# DISCRETE_IF.net
KiCad netlist of a schematic drawn in Altium Designer
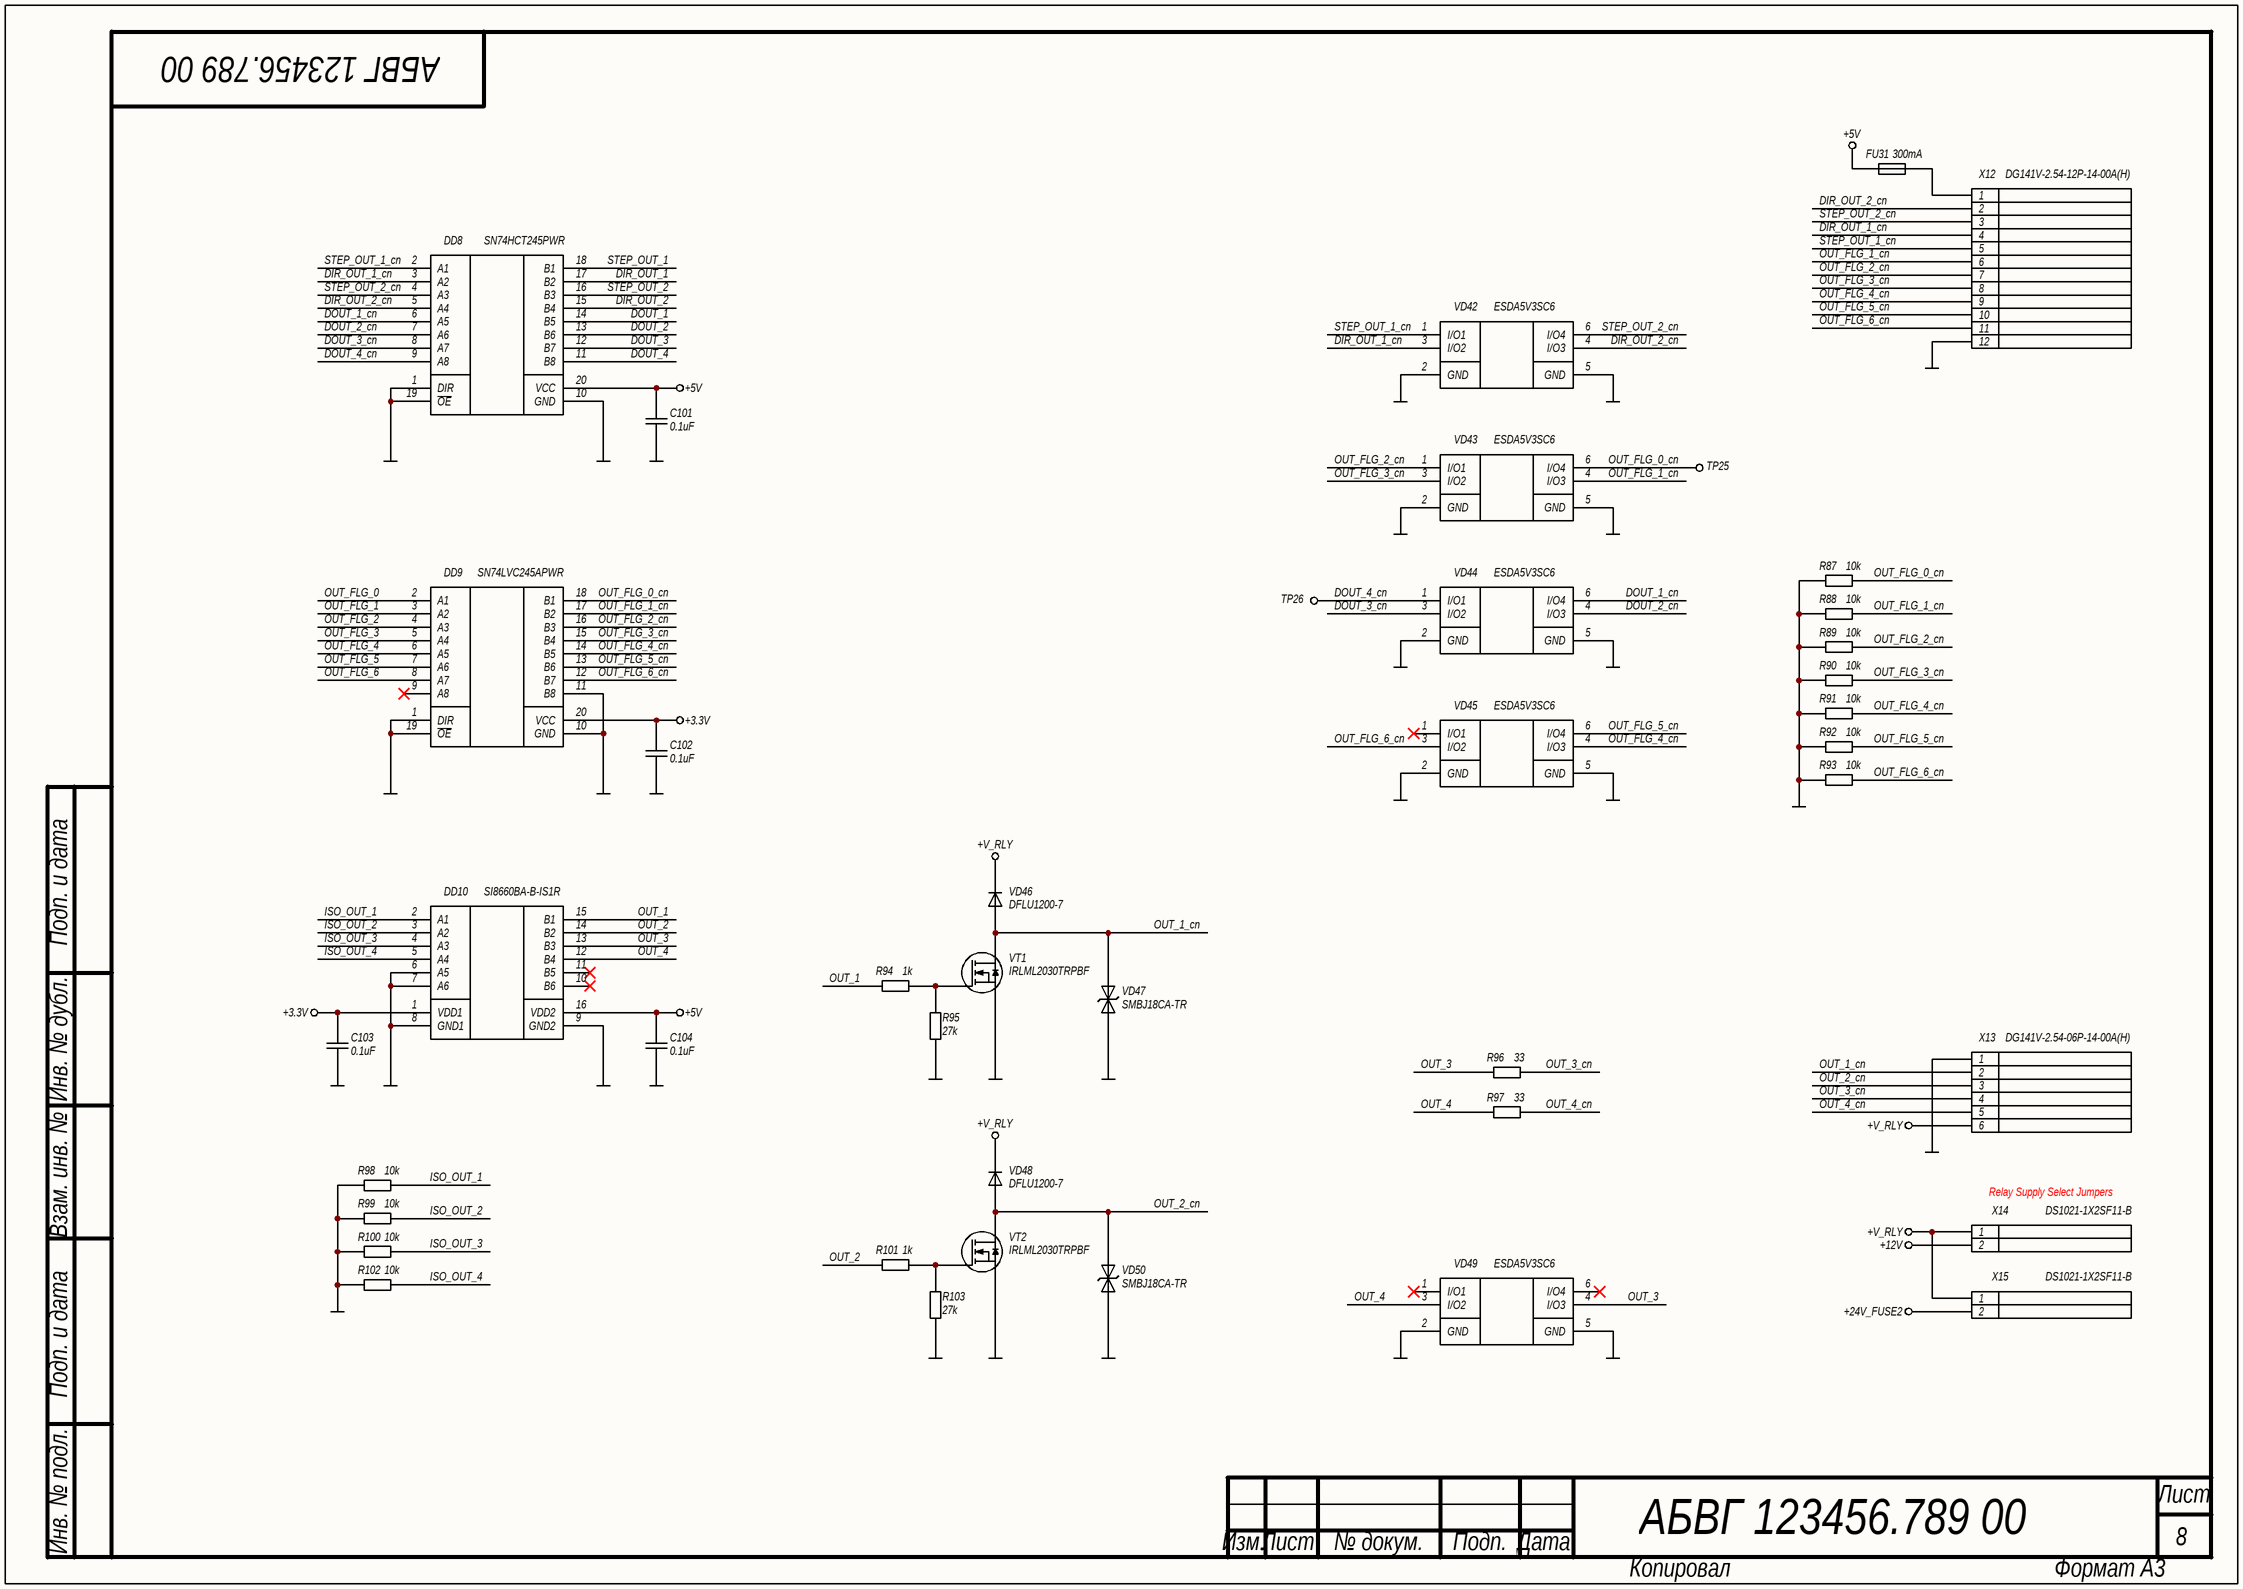
[diagram p0: DISCRETE_IF.SchDoc]

(export (version "E")
  (design (tool "Eeschema 10.0.6"))
  (components
    (comp (ref "C101")
      (value "0.1uF")
      (footprint "C0603N")
      (description "Конденсатор")
      (libsource (lib "Components Library") (part "CAP_FIXED"))
    )
    (comp (ref "C102")
      (value "0.1uF")
      (footprint "C0603N")
      (description "Конденсатор")
      (libsource (lib "Components Library") (part "CAP_FIXED"))
    )
    (comp (ref "C103")
      (value "0.1uF")
      (footprint "C0603N")
      (description "Конденсатор")
      (libsource (lib "Components Library") (part "CAP_FIXED"))
    )
    (comp (ref "C104")
      (value "0.1uF")
      (footprint "C0603N")
      (description "Конденсатор")
      (libsource (lib "Components Library") (part "CAP_FIXED"))
    )
    (comp (ref "DD8")
      (value "SN74HCT245PWR")
      (footprint "TSSOP20")
      (description "Микросхема шинный формирователь")
      (libsource (lib "Components Library") (part "SN74HCT245"))
    )
    (comp (ref "DD9")
      (value "SN74LVC245APWR")
      (footprint "TSSOP20")
      (description "Микросхема шинный формирователь")
      (libsource (lib "Components Library") (part "SN74LVC245"))
    )
    (comp (ref "DD10")
      (value "SI8660BA-B-IS1R")
      (footprint "SOIC16")
      (description "Микросхема цифровой изолятор")
      (libsource (lib "Components Library") (part "SI8660"))
    )
    (comp (ref "FU31")
      (value "300mA")
      (footprint "MF-MSMF")
      (description "Плавкий предохранитель")
      (libsource (lib "Components Library") (part "FUSE"))
    )
    (comp (ref "R87")
      (value "10k")
      (footprint "R0603N")
      (description "Резистор")
      (libsource (lib "Components Library") (part "RES_FIXED"))
    )
    (comp (ref "R88")
      (value "10k")
      (footprint "R0603N")
      (description "Резистор")
      (libsource (lib "Components Library") (part "RES_FIXED"))
    )
    (comp (ref "R89")
      (value "10k")
      (footprint "R0603N")
      (description "Резистор")
      (libsource (lib "Components Library") (part "RES_FIXED"))
    )
    (comp (ref "R90")
      (value "10k")
      (footprint "R0603N")
      (description "Резистор")
      (libsource (lib "Components Library") (part "RES_FIXED"))
    )
    (comp (ref "R91")
      (value "10k")
      (footprint "R0603N")
      (description "Резистор")
      (libsource (lib "Components Library") (part "RES_FIXED"))
    )
    (comp (ref "R92")
      (value "10k")
      (footprint "R0603N")
      (description "Резистор")
      (libsource (lib "Components Library") (part "RES_FIXED"))
    )
    (comp (ref "R93")
      (value "10k")
      (footprint "R0603N")
      (description "Резистор")
      (libsource (lib "Components Library") (part "RES_FIXED"))
    )
    (comp (ref "R94")
      (value "1k")
      (footprint "R0603N")
      (description "Резистор")
      (libsource (lib "Components Library") (part "RES_FIXED"))
    )
    (comp (ref "R95")
      (value "27k")
      (footprint "R0603N")
      (description "Резистор")
      (libsource (lib "") (part "RES_FIXED_1"))
    )
    (comp (ref "R96")
      (value "33")
      (footprint "R0603N")
      (description "Резистор")
      (libsource (lib "Components Library") (part "RES_FIXED"))
    )
    (comp (ref "R97")
      (value "33")
      (footprint "R0603N")
      (description "Резистор")
      (libsource (lib "Components Library") (part "RES_FIXED"))
    )
    (comp (ref "R98")
      (value "10k")
      (footprint "R0603N")
      (description "Резистор")
      (libsource (lib "Components Library") (part "RES_FIXED"))
    )
    (comp (ref "R99")
      (value "10k")
      (footprint "R0603N")
      (description "Резистор")
      (libsource (lib "Components Library") (part "RES_FIXED"))
    )
    (comp (ref "R100")
      (value "10k")
      (footprint "R0603N")
      (description "Резистор")
      (libsource (lib "Components Library") (part "RES_FIXED"))
    )
    (comp (ref "R101")
      (value "1k")
      (footprint "R0603N")
      (description "Резистор")
      (libsource (lib "Components Library") (part "RES_FIXED"))
    )
    (comp (ref "R102")
      (value "10k")
      (footprint "R0603N")
      (description "Резистор")
      (libsource (lib "Components Library") (part "RES_FIXED"))
    )
    (comp (ref "R103")
      (value "27k")
      (footprint "R0603N")
      (description "Резистор")
      (libsource (lib "") (part "RES_FIXED_1"))
    )
    (comp (ref "TP25")
      (value "TEST_POINT")
      (footprint "TP_HOLE_1MM_1.5MM")
      (description "Контрольная точка")
      (libsource (lib "Components Library") (part "TEST_POINT"))
    )
    (comp (ref "TP26")
      (value "TEST_POINT")
      (footprint "TP_HOLE_1MM_1.5MM")
      (description "Контрольная точка")
      (libsource (lib "Components Library") (part "TEST_POINT"))
    )
    (comp (ref "VD42")
      (value "ESDA5V3SC6")
      (footprint "SOT23-6")
      (description "Сборка TVS диодов, 4-канальная")
      (libsource (lib "Components Library") (part "ESDAxxSC6"))
    )
    (comp (ref "VD43")
      (value "ESDA5V3SC6")
      (footprint "SOT23-6")
      (description "Сборка TVS диодов, 4-канальная")
      (libsource (lib "Components Library") (part "ESDAxxSC6"))
    )
    (comp (ref "VD44")
      (value "ESDA5V3SC6")
      (footprint "SOT23-6")
      (description "Сборка TVS диодов, 4-канальная")
      (libsource (lib "Components Library") (part "ESDAxxSC6"))
    )
    (comp (ref "VD45")
      (value "ESDA5V3SC6")
      (footprint "SOT23-6")
      (description "Сборка TVS диодов, 4-канальная")
      (libsource (lib "Components Library") (part "ESDAxxSC6"))
    )
    (comp (ref "VD46")
      (value "DFLU1200-7")
      (footprint "PowerDI123")
      (description "Диод")
      (libsource (lib "Components Library") (part "DIODE"))
    )
    (comp (ref "VD47")
      (value "SMBJ18CA-TR")
      (footprint "SMB")
      (description "TVS диод двунаправленный")
      (libsource (lib "Components Library") (part "TVS_BIDIR"))
    )
    (comp (ref "VD48")
      (value "DFLU1200-7")
      (footprint "PowerDI123")
      (description "Диод")
      (libsource (lib "Components Library") (part "DIODE"))
    )
    (comp (ref "VD49")
      (value "ESDA5V3SC6")
      (footprint "SOT23-6")
      (description "Сборка TVS диодов, 4-канальная")
      (libsource (lib "Components Library") (part "ESDAxxSC6"))
    )
    (comp (ref "VD50")
      (value "SMBJ18CA-TR")
      (footprint "SMB")
      (description "TVS диод двунаправленный")
      (libsource (lib "Components Library") (part "TVS_BIDIR"))
    )
    (comp (ref "VT1")
      (value "IRLML2030TRPBF")
      (footprint "SOT23")
      (description "МОП транзистор, N-канальный")
      (libsource (lib "Components Library") (part "N-MOS 3 LEADS_G1"))
    )
    (comp (ref "VT2")
      (value "IRLML2030TRPBF")
      (footprint "SOT23")
      (description "МОП транзистор, N-канальный")
      (libsource (lib "Components Library") (part "N-MOS 3 LEADS_G1"))
    )
    (comp (ref "X12")
      (value "DG141V-2.54-12P-14-00A(H)")
      (footprint "DG141V-2.54-12P-14-00A(H)")
      (description "Разъем, 12 контактов")
      (libsource (lib "Components Library") (part "Connector 12"))
    )
    (comp (ref "X13")
      (value "DG141V-2.54-06P-14-00A(H)")
      (footprint "DG141V-2.54-06P-14-00A(H)")
      (description "Разъем, 6 контактов")
      (libsource (lib "Components Library") (part "Connector 6"))
    )
    (comp (ref "X14")
      (value "DS1021-1X2SF11-B")
      (footprint "2.54_2X1_HEADER")
      (description "Разъем, 2 контакта")
      (libsource (lib "Components Library") (part "Connector 2"))
    )
    (comp (ref "X15")
      (value "DS1021-1X2SF11-B")
      (footprint "2.54_2X1_HEADER")
      (description "Разъем, 2 контакта")
      (libsource (lib "Components Library") (part "Connector 2"))
    )
  )
  (nets
    (net (code "1") (name "+3.3V") (class "Default")
      (node (ref "C102") (pin "2") (pinfunction "2_2") (pintype "passive"))
      (node (ref "C103") (pin "2") (pinfunction "2_2") (pintype "passive"))
      (node (ref "DD10") (pin "1") (pinfunction "VDD1_1") (pintype "power_in"))
      (node (ref "DD9") (pin "20") (pinfunction "VCC_20") (pintype "power_in"))
    )
    (net (code "2") (name "+5V") (class "Default")
      (node (ref "C101") (pin "2") (pinfunction "2_2") (pintype "passive"))
      (node (ref "C104") (pin "2") (pinfunction "2_2") (pintype "passive"))
      (node (ref "DD10") (pin "16") (pinfunction "VDD2_16") (pintype "power_in"))
      (node (ref "DD8") (pin "20") (pinfunction "VCC_20") (pintype "power_in"))
      (node (ref "FU31") (pin "1") (pinfunction "1_1") (pintype "passive"))
    )
    (net (code "3") (name "+12V") (class "Default")
      (node (ref "X14") (pin "2") (pinfunction "2_2") (pintype "power_in"))
    )
    (net (code "4") (name "+24V_FUSE2") (class "Default")
      (node (ref "X15") (pin "2") (pinfunction "2_2") (pintype "power_in"))
    )
    (net (code "5") (name "+V_RLY") (class "Default")
      (node (ref "VD46") (pin "1") (pinfunction "K_1") (pintype "passive"))
      (node (ref "VD48") (pin "1") (pinfunction "K_1") (pintype "passive"))
      (node (ref "X13") (pin "6") (pinfunction "6_6") (pintype "power_in"))
      (node (ref "X14") (pin "1") (pinfunction "1_1") (pintype "power_in"))
      (node (ref "X15") (pin "1") (pinfunction "1_1") (pintype "power_in"))
    )
    (net (code "6") (name "/DIR_OUT_1") (class "Default")
      (node (ref "DD8") (pin "17") (pinfunction "B2_17") (pintype "power_in"))
    )
    (net (code "7") (name "/DIR_OUT_1_cn") (class "Default")
      (node (ref "DD8") (pin "3") (pinfunction "A2_3") (pintype "power_in"))
      (node (ref "VD42") (pin "3") (pinfunction "I/O2_3") (pintype "power_in"))
      (node (ref "X12") (pin "4") (pinfunction "4_4") (pintype "power_in"))
    )
    (net (code "8") (name "/DIR_OUT_2") (class "Default")
      (node (ref "DD8") (pin "15") (pinfunction "B4_15") (pintype "power_in"))
    )
    (net (code "9") (name "/DIR_OUT_2_cn") (class "Default")
      (node (ref "DD8") (pin "5") (pinfunction "A4_5") (pintype "power_in"))
      (node (ref "VD42") (pin "4") (pinfunction "I/O3_4") (pintype "power_in"))
      (node (ref "X12") (pin "2") (pinfunction "2_2") (pintype "power_in"))
    )
    (net (code "10") (name "/DOUT_1") (class "Default")
      (node (ref "DD8") (pin "14") (pinfunction "B5_14") (pintype "power_in"))
    )
    (net (code "11") (name "/DOUT_1_cn") (class "Default")
      (node (ref "DD8") (pin "6") (pinfunction "A5_6") (pintype "power_in"))
      (node (ref "VD44") (pin "6") (pinfunction "I/O4_6") (pintype "power_in"))
    )
    (net (code "12") (name "/DOUT_2") (class "Default")
      (node (ref "DD8") (pin "13") (pinfunction "B6_13") (pintype "power_in"))
    )
    (net (code "13") (name "/DOUT_2_cn") (class "Default")
      (node (ref "DD8") (pin "7") (pinfunction "A6_7") (pintype "power_in"))
      (node (ref "VD44") (pin "4") (pinfunction "I/O3_4") (pintype "power_in"))
    )
    (net (code "14") (name "/DOUT_3") (class "Default")
      (node (ref "DD8") (pin "12") (pinfunction "B7_12") (pintype "power_in"))
    )
    (net (code "15") (name "/DOUT_3_cn") (class "Default")
      (node (ref "DD8") (pin "8") (pinfunction "A7_8") (pintype "power_in"))
      (node (ref "VD44") (pin "3") (pinfunction "I/O2_3") (pintype "power_in"))
    )
    (net (code "16") (name "/DOUT_4") (class "Default")
      (node (ref "DD8") (pin "11") (pinfunction "B8_11") (pintype "power_in"))
    )
    (net (code "17") (name "/DOUT_4_cn") (class "Default")
      (node (ref "DD8") (pin "9") (pinfunction "A8_9") (pintype "power_in"))
      (node (ref "TP26") (pin "1") (pinfunction "1_1") (pintype "passive"))
      (node (ref "VD44") (pin "1") (pinfunction "I/O1_1") (pintype "power_in"))
    )
    (net (code "18") (name "/ISO_OUT_1") (class "Default")
      (node (ref "DD10") (pin "2") (pinfunction "A1_2") (pintype "power_in"))
      (node (ref "R98") (pin "1") (pinfunction "1_1") (pintype "passive"))
    )
    (net (code "19") (name "/ISO_OUT_2") (class "Default")
      (node (ref "DD10") (pin "3") (pinfunction "A2_3") (pintype "power_in"))
      (node (ref "R99") (pin "1") (pinfunction "1_1") (pintype "passive"))
    )
    (net (code "20") (name "/ISO_OUT_3") (class "Default")
      (node (ref "DD10") (pin "4") (pinfunction "A3_4") (pintype "power_in"))
      (node (ref "R100") (pin "1") (pinfunction "1_1") (pintype "passive"))
    )
    (net (code "21") (name "/ISO_OUT_4") (class "Default")
      (node (ref "DD10") (pin "5") (pinfunction "A4_5") (pintype "power_in"))
      (node (ref "R102") (pin "1") (pinfunction "1_1") (pintype "passive"))
    )
    (net (code "22") (name "/OUT_1") (class "Default")
      (node (ref "DD10") (pin "15") (pinfunction "B1_15") (pintype "power_in"))
      (node (ref "R94") (pin "2") (pinfunction "2_2") (pintype "passive"))
    )
    (net (code "23") (name "/OUT_1_cn") (class "Default")
      (node (ref "VD46") (pin "2") (pinfunction "A_2") (pintype "passive"))
      (node (ref "VD47") (pin "1") (pinfunction "A1_1") (pintype "passive"))
      (node (ref "VT1") (pin "3") (pinfunction "D_3") (pintype "passive"))
      (node (ref "X13") (pin "2") (pinfunction "2_2") (pintype "power_in"))
    )
    (net (code "24") (name "/OUT_2") (class "Default")
      (node (ref "DD10") (pin "14") (pinfunction "B2_14") (pintype "power_in"))
      (node (ref "R101") (pin "2") (pinfunction "2_2") (pintype "passive"))
    )
    (net (code "25") (name "/OUT_2_cn") (class "Default")
      (node (ref "VD48") (pin "2") (pinfunction "A_2") (pintype "passive"))
      (node (ref "VD50") (pin "1") (pinfunction "A1_1") (pintype "passive"))
      (node (ref "VT2") (pin "3") (pinfunction "D_3") (pintype "passive"))
      (node (ref "X13") (pin "3") (pinfunction "3_3") (pintype "power_in"))
    )
    (net (code "26") (name "/OUT_3") (class "Default")
      (node (ref "DD10") (pin "13") (pinfunction "B3_13") (pintype "power_in"))
      (node (ref "R96") (pin "2") (pinfunction "2_2") (pintype "passive"))
      (node (ref "VD49") (pin "4") (pinfunction "I/O3_4") (pintype "power_in"))
    )
    (net (code "27") (name "/OUT_3_cn") (class "Default")
      (node (ref "R96") (pin "1") (pinfunction "1_1") (pintype "passive"))
      (node (ref "X13") (pin "4") (pinfunction "4_4") (pintype "power_in"))
    )
    (net (code "28") (name "/OUT_4") (class "Default")
      (node (ref "DD10") (pin "12") (pinfunction "B4_12") (pintype "power_in"))
      (node (ref "R97") (pin "2") (pinfunction "2_2") (pintype "passive"))
      (node (ref "VD49") (pin "3") (pinfunction "I/O2_3") (pintype "power_in"))
    )
    (net (code "29") (name "/OUT_4_cn") (class "Default")
      (node (ref "R97") (pin "1") (pinfunction "1_1") (pintype "passive"))
      (node (ref "X13") (pin "5") (pinfunction "5_5") (pintype "power_in"))
    )
    (net (code "30") (name "/OUT_FLG_0") (class "Default")
      (node (ref "DD9") (pin "2") (pinfunction "A1_2") (pintype "power_in"))
    )
    (net (code "31") (name "/OUT_FLG_0_cn") (class "Default")
      (node (ref "DD9") (pin "18") (pinfunction "B1_18") (pintype "power_in"))
      (node (ref "R87") (pin "1") (pinfunction "1_1") (pintype "passive"))
      (node (ref "TP25") (pin "1") (pinfunction "1_1") (pintype "passive"))
      (node (ref "VD43") (pin "6") (pinfunction "I/O4_6") (pintype "power_in"))
    )
    (net (code "32") (name "/OUT_FLG_1") (class "Default")
      (node (ref "DD9") (pin "3") (pinfunction "A2_3") (pintype "power_in"))
    )
    (net (code "33") (name "/OUT_FLG_1_cn") (class "Default")
      (node (ref "DD9") (pin "17") (pinfunction "B2_17") (pintype "power_in"))
      (node (ref "R88") (pin "1") (pinfunction "1_1") (pintype "passive"))
      (node (ref "VD43") (pin "4") (pinfunction "I/O3_4") (pintype "power_in"))
      (node (ref "X12") (pin "6") (pinfunction "6_6") (pintype "power_in"))
    )
    (net (code "34") (name "/OUT_FLG_2") (class "Default")
      (node (ref "DD9") (pin "4") (pinfunction "A3_4") (pintype "power_in"))
    )
    (net (code "35") (name "/OUT_FLG_2_cn") (class "Default")
      (node (ref "DD9") (pin "16") (pinfunction "B3_16") (pintype "power_in"))
      (node (ref "R89") (pin "1") (pinfunction "1_1") (pintype "passive"))
      (node (ref "VD43") (pin "1") (pinfunction "I/O1_1") (pintype "power_in"))
      (node (ref "X12") (pin "7") (pinfunction "7_7") (pintype "power_in"))
    )
    (net (code "36") (name "/OUT_FLG_3") (class "Default")
      (node (ref "DD9") (pin "5") (pinfunction "A4_5") (pintype "power_in"))
    )
    (net (code "37") (name "/OUT_FLG_3_cn") (class "Default")
      (node (ref "DD9") (pin "15") (pinfunction "B4_15") (pintype "power_in"))
      (node (ref "R90") (pin "1") (pinfunction "1_1") (pintype "passive"))
      (node (ref "VD43") (pin "3") (pinfunction "I/O2_3") (pintype "power_in"))
      (node (ref "X12") (pin "8") (pinfunction "8_8") (pintype "power_in"))
    )
    (net (code "38") (name "/OUT_FLG_4") (class "Default")
      (node (ref "DD9") (pin "6") (pinfunction "A5_6") (pintype "power_in"))
    )
    (net (code "39") (name "/OUT_FLG_4_cn") (class "Default")
      (node (ref "DD9") (pin "14") (pinfunction "B5_14") (pintype "power_in"))
      (node (ref "R91") (pin "1") (pinfunction "1_1") (pintype "passive"))
      (node (ref "VD45") (pin "4") (pinfunction "I/O3_4") (pintype "power_in"))
      (node (ref "X12") (pin "9") (pinfunction "9_9") (pintype "power_in"))
    )
    (net (code "40") (name "/OUT_FLG_5") (class "Default")
      (node (ref "DD9") (pin "7") (pinfunction "A6_7") (pintype "power_in"))
    )
    (net (code "41") (name "/OUT_FLG_5_cn") (class "Default")
      (node (ref "DD9") (pin "13") (pinfunction "B6_13") (pintype "power_in"))
      (node (ref "R92") (pin "1") (pinfunction "1_1") (pintype "passive"))
      (node (ref "VD45") (pin "6") (pinfunction "I/O4_6") (pintype "power_in"))
      (node (ref "X12") (pin "10") (pinfunction "10_10") (pintype "power_in"))
    )
    (net (code "42") (name "/OUT_FLG_6") (class "Default")
      (node (ref "DD9") (pin "8") (pinfunction "A7_8") (pintype "power_in"))
    )
    (net (code "43") (name "/OUT_FLG_6_cn") (class "Default")
      (node (ref "DD9") (pin "12") (pinfunction "B7_12") (pintype "power_in"))
      (node (ref "R93") (pin "1") (pinfunction "1_1") (pintype "passive"))
      (node (ref "VD45") (pin "3") (pinfunction "I/O2_3") (pintype "power_in"))
      (node (ref "X12") (pin "11") (pinfunction "11_11") (pintype "power_in"))
    )
    (net (code "44") (name "/STEP_OUT_1") (class "Default")
      (node (ref "DD8") (pin "18") (pinfunction "B1_18") (pintype "power_in"))
    )
    (net (code "45") (name "/STEP_OUT_1_cn") (class "Default")
      (node (ref "DD8") (pin "2") (pinfunction "A1_2") (pintype "power_in"))
      (node (ref "VD42") (pin "1") (pinfunction "I/O1_1") (pintype "power_in"))
      (node (ref "X12") (pin "5") (pinfunction "5_5") (pintype "power_in"))
    )
    (net (code "46") (name "/STEP_OUT_2") (class "Default")
      (node (ref "DD8") (pin "16") (pinfunction "B3_16") (pintype "power_in"))
    )
    (net (code "47") (name "/STEP_OUT_2_cn") (class "Default")
      (node (ref "DD8") (pin "4") (pinfunction "A3_4") (pintype "power_in"))
      (node (ref "VD42") (pin "6") (pinfunction "I/O4_6") (pintype "power_in"))
      (node (ref "X12") (pin "3") (pinfunction "3_3") (pintype "power_in"))
    )
    (net (code "48") (name "GND") (class "Default")
      (node (ref "C101") (pin "1") (pinfunction "1_1") (pintype "passive"))
      (node (ref "C102") (pin "1") (pinfunction "1_1") (pintype "passive"))
      (node (ref "C103") (pin "1") (pinfunction "1_1") (pintype "passive"))
      (node (ref "C104") (pin "1") (pinfunction "1_1") (pintype "passive"))
      (node (ref "DD10") (pin "6") (pinfunction "A5_6") (pintype "power_in"))
      (node (ref "DD10") (pin "7") (pinfunction "A6_7") (pintype "power_in"))
      (node (ref "DD10") (pin "8") (pinfunction "GND1_8") (pintype "power_in"))
      (node (ref "DD10") (pin "9") (pinfunction "GND2_9") (pintype "power_in"))
      (node (ref "DD8") (pin "1") (pinfunction "DIR_1") (pintype "power_in"))
      (node (ref "DD8") (pin "10") (pinfunction "GND_10") (pintype "power_in"))
      (node (ref "DD8") (pin "19") (pinfunction "~{OE}_19") (pintype "power_in"))
      (node (ref "DD9") (pin "1") (pinfunction "DIR_1") (pintype "power_in"))
      (node (ref "DD9") (pin "10") (pinfunction "GND_10") (pintype "power_in"))
      (node (ref "DD9") (pin "11") (pinfunction "B8_11") (pintype "power_in"))
      (node (ref "DD9") (pin "19") (pinfunction "~{OE}_19") (pintype "power_in"))
      (node (ref "R100") (pin "2") (pinfunction "2_2") (pintype "passive"))
      (node (ref "R102") (pin "2") (pinfunction "2_2") (pintype "passive"))
      (node (ref "R103") (pin "1") (pinfunction "1_1") (pintype "passive"))
      (node (ref "R87") (pin "2") (pinfunction "2_2") (pintype "passive"))
      (node (ref "R88") (pin "2") (pinfunction "2_2") (pintype "passive"))
      (node (ref "R89") (pin "2") (pinfunction "2_2") (pintype "passive"))
      (node (ref "R90") (pin "2") (pinfunction "2_2") (pintype "passive"))
      (node (ref "R91") (pin "2") (pinfunction "2_2") (pintype "passive"))
      (node (ref "R92") (pin "2") (pinfunction "2_2") (pintype "passive"))
      (node (ref "R93") (pin "2") (pinfunction "2_2") (pintype "passive"))
      (node (ref "R95") (pin "1") (pinfunction "1_1") (pintype "passive"))
      (node (ref "R98") (pin "2") (pinfunction "2_2") (pintype "passive"))
      (node (ref "R99") (pin "2") (pinfunction "2_2") (pintype "passive"))
      (node (ref "VD42") (pin "2") (pinfunction "GND_2") (pintype "power_in"))
      (node (ref "VD42") (pin "5") (pinfunction "GND_5") (pintype "power_in"))
      (node (ref "VD43") (pin "2") (pinfunction "GND_2") (pintype "power_in"))
      (node (ref "VD43") (pin "5") (pinfunction "GND_5") (pintype "power_in"))
      (node (ref "VD44") (pin "2") (pinfunction "GND_2") (pintype "power_in"))
      (node (ref "VD44") (pin "5") (pinfunction "GND_5") (pintype "power_in"))
      (node (ref "VD45") (pin "2") (pinfunction "GND_2") (pintype "power_in"))
      (node (ref "VD45") (pin "5") (pinfunction "GND_5") (pintype "power_in"))
      (node (ref "VD47") (pin "2") (pinfunction "A2_2") (pintype "passive"))
      (node (ref "VD49") (pin "2") (pinfunction "GND_2") (pintype "power_in"))
      (node (ref "VD49") (pin "5") (pinfunction "GND_5") (pintype "power_in"))
      (node (ref "VD50") (pin "2") (pinfunction "A2_2") (pintype "passive"))
      (node (ref "VT1") (pin "2") (pinfunction "S_2") (pintype "passive"))
      (node (ref "VT2") (pin "2") (pinfunction "S_2") (pintype "passive"))
      (node (ref "X12") (pin "12") (pinfunction "12_12") (pintype "power_in"))
      (node (ref "X13") (pin "1") (pinfunction "1_1") (pintype "power_in"))
    )
    (net (code "49") (name "Net-(FU31-Pad2)") (class "Default")
      (node (ref "FU31") (pin "2") (pinfunction "2_2") (pintype "passive"))
      (node (ref "X12") (pin "1") (pinfunction "1_1") (pintype "power_in"))
    )
    (net (code "50") (name "Net-(VT1-G)") (class "Default")
      (node (ref "R94") (pin "1") (pinfunction "1_1") (pintype "passive"))
      (node (ref "R95") (pin "2") (pinfunction "2_2") (pintype "passive"))
      (node (ref "VT1") (pin "1") (pinfunction "G_1") (pintype "passive"))
    )
    (net (code "51") (name "Net-(VT2-G)") (class "Default")
      (node (ref "R101") (pin "1") (pinfunction "1_1") (pintype "passive"))
      (node (ref "R103") (pin "2") (pinfunction "2_2") (pintype "passive"))
      (node (ref "VT2") (pin "1") (pinfunction "G_1") (pintype "passive"))
    )
    (net (code "52") (name "unconnected-(DD9-A8-Pad9)") (class "Default")
      (node (ref "DD9") (pin "9") (pinfunction "A8_9") (pintype "power_in+no_connect"))
    )
    (net (code "53") (name "unconnected-(DD10-B5-Pad11)") (class "Default")
      (node (ref "DD10") (pin "11") (pinfunction "B5_11") (pintype "power_in+no_connect"))
    )
    (net (code "54") (name "unconnected-(DD10-B6-Pad10)") (class "Default")
      (node (ref "DD10") (pin "10") (pinfunction "B6_10") (pintype "power_in+no_connect"))
    )
    (net (code "55") (name "unconnected-(VD45-I{slash}O1-Pad1)") (class "Default")
      (node (ref "VD45") (pin "1") (pinfunction "I/O1_1") (pintype "power_in+no_connect"))
    )
    (net (code "56") (name "unconnected-(VD49-I{slash}O1-Pad1)") (class "Default")
      (node (ref "VD49") (pin "1") (pinfunction "I/O1_1") (pintype "power_in+no_connect"))
    )
    (net (code "57") (name "unconnected-(VD49-I{slash}O4-Pad6)") (class "Default")
      (node (ref "VD49") (pin "6") (pinfunction "I/O4_6") (pintype "power_in+no_connect"))
    )
  )
)
